# sensorFreezer.net
KiCad netlist of a schematic drawn in EAGLE
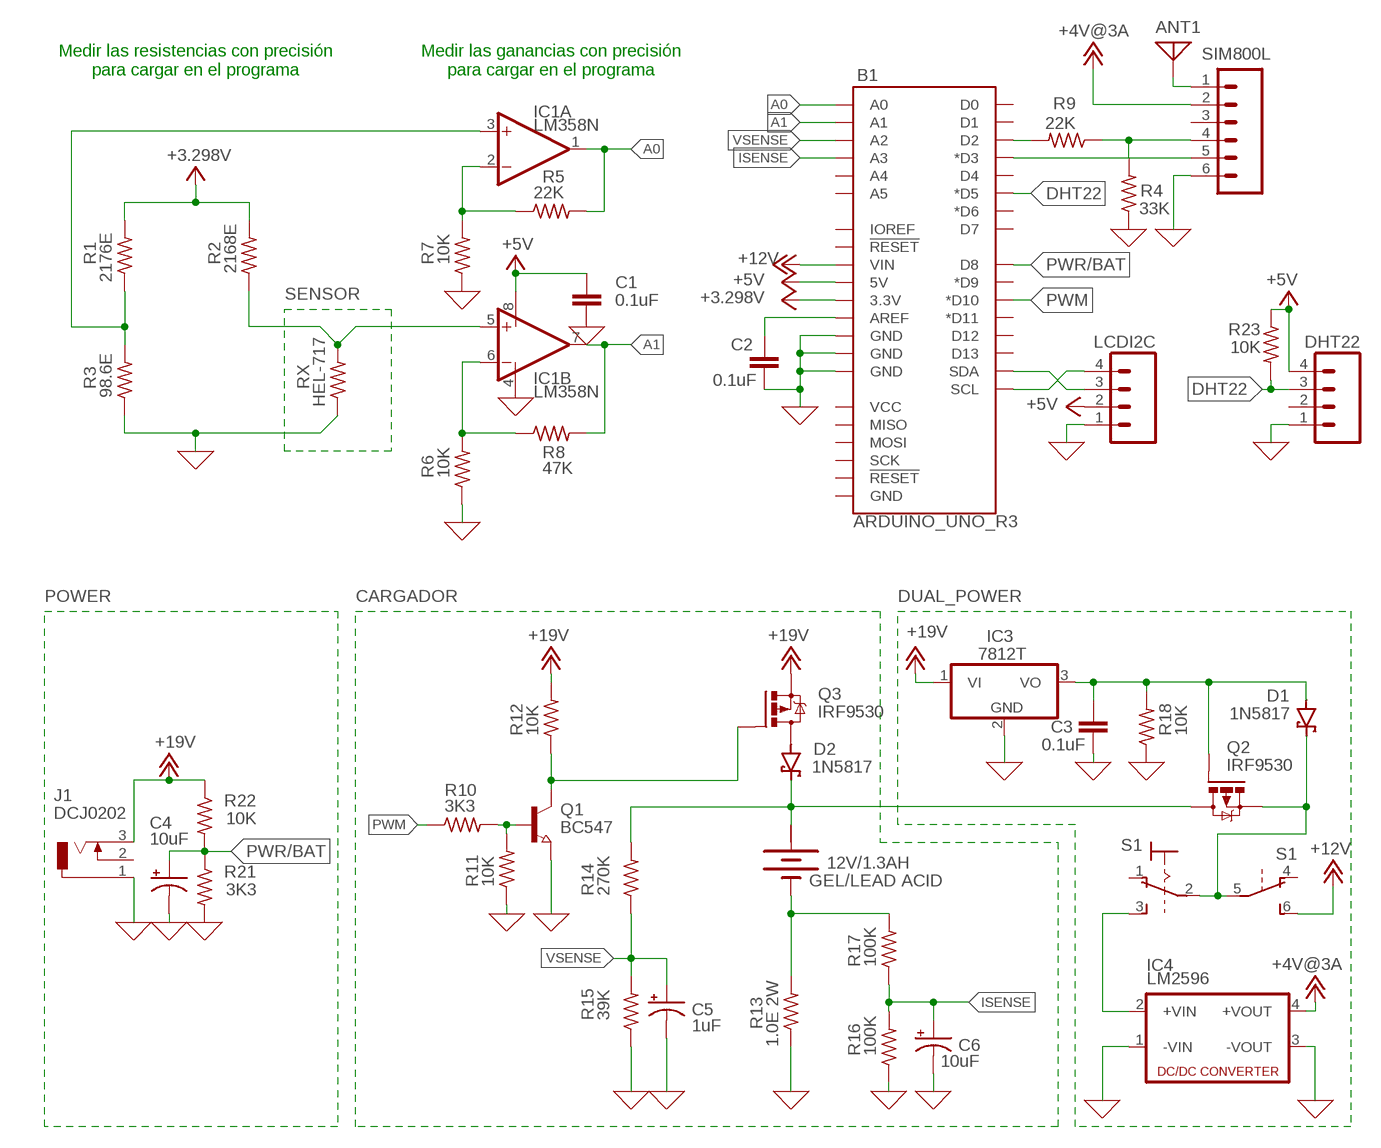
[diagram p0: schematic, sheet 1]

(export (version "E")
  (design (tool "Eeschema 10.0.6"))
  (components
    (comp (ref "12V/1.3AH")
      (value "GEL/LEAD ACID")
      (footprint "eagle-import:BATTERY")
      (libsource (lib "eagle-import") (part "BATTERY"))
    )
    (comp (ref "ANT1")
      (value "ANTENNA")
      (footprint "eagle-import:PAD-01")
      (libsource (lib "eagle-import") (part "ANTENNA"))
    )
    (comp (ref "B1")
      (value "ARDUINO_UNO_R3")
      (footprint "eagle-import:ARDUINO_R3")
      (libsource (lib "eagle-import") (part "ARDUINO_UNO_R3"))
    )
    (comp (ref "C1")
      (value "0.1uF")
      (footprint "eagle-import:C2.5-3")
      (libsource (lib "eagle-import") (part "C2,5-3"))
    )
    (comp (ref "C2")
      (value "0.1uF")
      (footprint "eagle-import:C2.5-3")
      (libsource (lib "eagle-import") (part "C2,5-3"))
    )
    (comp (ref "C3")
      (value "0.1uF")
      (footprint "eagle-import:C2.5-3")
      (libsource (lib "eagle-import") (part "C2,5-3"))
    )
    (comp (ref "C4")
      (value "10uF")
      (footprint "eagle-import:085CS_1AR")
      (libsource (lib "eagle-import") (part "CPOL-US085CS-1AR"))
    )
    (comp (ref "C5")
      (value "1uF")
      (footprint "eagle-import:085CS_1AR")
      (libsource (lib "eagle-import") (part "CPOL-US085CS-1AR"))
    )
    (comp (ref "C6")
      (value "10uF")
      (footprint "eagle-import:085CS_1AR")
      (libsource (lib "eagle-import") (part "CPOL-US085CS-1AR"))
    )
    (comp (ref "D1")
      (value "1N5817")
      (footprint "eagle-import:DO41-7.6")
      (libsource (lib "eagle-import") (part "1N5819-B"))
    )
    (comp (ref "D2")
      (value "1N5817")
      (footprint "eagle-import:DO41-7.6")
      (libsource (lib "eagle-import") (part "1N5819-B"))
    )
    (comp (ref "DHT22")
      (value "M04")
      (footprint "eagle-import:04P")
      (libsource (lib "eagle-import") (part "M04"))
    )
    (comp (ref "IC1")
      (value "LM358N")
      (footprint "eagle-import:DIL08")
      (libsource (lib "eagle-import") (part "LM358N"))
    )
    (comp (ref "IC3")
      (value "7812T")
      (footprint "eagle-import:TO220H")
      (libsource (lib "eagle-import") (part "78T12"))
    )
    (comp (ref "IC4")
      (value "LM2596")
      (footprint "eagle-import:NME")
      (fields (field (name "MF") "C & D TECHNOLOGIES, INC") (field (name "MPN") "NME1205D"))
      (libsource (lib "eagle-import") (part "NME"))
    )
    (comp (ref "J1")
      (value "DCJ0202")
      (footprint "eagle-import:DCJ0202")
      (libsource (lib "eagle-import") (part "DCJ0202"))
    )
    (comp (ref "LCDI2C")
      (value "M04")
      (footprint "eagle-import:04P")
      (libsource (lib "eagle-import") (part "M04"))
    )
    (comp (ref "Q1")
      (value "BC547")
      (footprint "eagle-import:SOT23")
      (libsource (lib "eagle-import") (part "NPN-TRANSISTOR_SOT23"))
    )
    (comp (ref "Q2")
      (value "IRF9530")
      (footprint "eagle-import:TO220BV")
      (libsource (lib "eagle-import") (part "IRF9530"))
    )
    (comp (ref "Q3")
      (value "IRF9530")
      (footprint "eagle-import:TO220BV")
      (libsource (lib "eagle-import") (part "IRF9530"))
    )
    (comp (ref "R1")
      (value "2176E")
      (footprint "eagle-import:0204_5")
      (libsource (lib "eagle-import") (part "R-US_0204/5"))
    )
    (comp (ref "R2")
      (value "2168E")
      (footprint "eagle-import:0204_5")
      (libsource (lib "eagle-import") (part "R-US_0204/5"))
    )
    (comp (ref "R3")
      (value "98.6E")
      (footprint "eagle-import:0204_5")
      (libsource (lib "eagle-import") (part "R-US_0204/5"))
    )
    (comp (ref "R4")
      (value "33K")
      (footprint "eagle-import:0204_5")
      (libsource (lib "eagle-import") (part "R-US_0204/5"))
    )
    (comp (ref "R5")
      (value "22K")
      (footprint "eagle-import:0204_5")
      (libsource (lib "eagle-import") (part "R-US_0204/5"))
    )
    (comp (ref "R6")
      (value "10K")
      (footprint "eagle-import:0204_5")
      (libsource (lib "eagle-import") (part "R-US_0204/5"))
    )
    (comp (ref "R7")
      (value "10K")
      (footprint "eagle-import:0204_5")
      (libsource (lib "eagle-import") (part "R-US_0204/5"))
    )
    (comp (ref "R8")
      (value "47K")
      (footprint "eagle-import:0204_5")
      (libsource (lib "eagle-import") (part "R-US_0204/5"))
    )
    (comp (ref "R9")
      (value "22K")
      (footprint "eagle-import:0204_5")
      (libsource (lib "eagle-import") (part "R-US_0204/5"))
    )
    (comp (ref "R10")
      (value "3K3")
      (footprint "eagle-import:0204_5")
      (libsource (lib "eagle-import") (part "R-US_0204/5"))
    )
    (comp (ref "R11")
      (value "10K")
      (footprint "eagle-import:0204_5")
      (libsource (lib "eagle-import") (part "R-US_0204/5"))
    )
    (comp (ref "R12")
      (value "10K")
      (footprint "eagle-import:0204_5")
      (libsource (lib "eagle-import") (part "R-US_0204/5"))
    )
    (comp (ref "R13")
      (value "1.0E 2W")
      (footprint "eagle-import:0204_5")
      (libsource (lib "eagle-import") (part "R-US_0204/5"))
    )
    (comp (ref "R14")
      (value "270K")
      (footprint "eagle-import:0204_5")
      (libsource (lib "eagle-import") (part "R-US_0204/5"))
    )
    (comp (ref "R15")
      (value "39K")
      (footprint "eagle-import:0204_5")
      (libsource (lib "eagle-import") (part "R-US_0204/5"))
    )
    (comp (ref "R16")
      (value "100K")
      (footprint "eagle-import:0204_5")
      (libsource (lib "eagle-import") (part "R-US_0204/5"))
    )
    (comp (ref "R17")
      (value "100K")
      (footprint "eagle-import:0204_5")
      (libsource (lib "eagle-import") (part "R-US_0204/5"))
    )
    (comp (ref "R18")
      (value "10K")
      (footprint "eagle-import:0204_5")
      (libsource (lib "eagle-import") (part "R-US_0204/5"))
    )
    (comp (ref "R21")
      (value "3K3")
      (footprint "eagle-import:0204_5")
      (libsource (lib "eagle-import") (part "R-US_0204/5"))
    )
    (comp (ref "R22")
      (value "10K")
      (footprint "eagle-import:0204_5")
      (libsource (lib "eagle-import") (part "R-US_0204/5"))
    )
    (comp (ref "R23")
      (value "10K")
      (footprint "eagle-import:0204_5")
      (libsource (lib "eagle-import") (part "R-US_0204/5"))
    )
    (comp (ref "RX")
      (value "HEL-717")
      (footprint "eagle-import:0204_5")
      (libsource (lib "eagle-import") (part "R-US_0204/5"))
    )
    (comp (ref "S1")
      (value "320-938")
      (footprint "eagle-import:320-938")
      (libsource (lib "eagle-import") (part "320-938"))
    )
    (comp (ref "SIM800L")
      (value "M06")
      (footprint "eagle-import:06P")
      (libsource (lib "eagle-import") (part "M06"))
    )
  )
  (nets
    (net (code "1") (name "+3.298V") (class "Default")
      (node (ref "B1") (pin "3.3V") (pinfunction "3.3V_3.3V") (pintype "bidirectional"))
      (node (ref "R1") (pin "2") (pinfunction "2_2") (pintype "passive"))
      (node (ref "R2") (pin "2") (pinfunction "2_2") (pintype "passive"))
    )
    (net (code "2") (name "+5V") (class "Default")
      (node (ref "B1") (pin "5V") (pinfunction "5V_5V") (pintype "bidirectional"))
      (node (ref "C1") (pin "1") (pinfunction "1_1") (pintype "passive"))
      (node (ref "DHT22") (pin "4") (pinfunction "4_4") (pintype "passive"))
      (node (ref "IC1") (pin "8") (pinfunction "V+_8") (pintype "power_in"))
      (node (ref "LCDI2C") (pin "2") (pinfunction "2_2") (pintype "passive"))
      (node (ref "R23") (pin "1") (pinfunction "1_1") (pintype "passive"))
    )
    (net (code "3") (name "+12V") (class "Default")
      (node (ref "B1") (pin "VIN") (pinfunction "VIN_VIN") (pintype "bidirectional"))
      (node (ref "IC3") (pin "1") (pinfunction "VI_1") (pintype "input"))
      (node (ref "IC4") (pin "4") (pinfunction "+VOUT_4") (pintype "passive"))
      (node (ref "J1") (pin "3") (pinfunction "3_3") (pintype "passive"))
      (node (ref "Q3") (pin "S") (pinfunction "S_S") (pintype "passive"))
      (node (ref "R12") (pin "2") (pinfunction "2_2") (pintype "passive"))
      (node (ref "R22") (pin "1") (pinfunction "1_1") (pintype "passive"))
      (node (ref "S1") (pin "6") (pinfunction "S_6") (pintype "passive"))
      (node (ref "SIM800L") (pin "2") (pinfunction "2_2") (pintype "passive"))
    )
    (net (code "4") (name "/+") (class "Default")
      (node (ref "12V/1.3AH") (pin "+@1") (pinfunction "+_+@1") (pintype "power_in"))
    )
    (net (code "9") (name "A0") (class "Default")
      (node (ref "B1") (pin "A0") (pinfunction "A0_A0") (pintype "bidirectional"))
      (node (ref "IC1") (pin "1") (pinfunction "OUT_1") (pintype "output"))
      (node (ref "R5") (pin "2") (pinfunction "2_2") (pintype "passive"))
    )
    (net (code "10") (name "A1") (class "Default")
      (node (ref "B1") (pin "A1") (pinfunction "A1_A1") (pintype "bidirectional"))
      (node (ref "IC1") (pin "7") (pinfunction "OUT_7") (pintype "output"))
      (node (ref "R8") (pin "2") (pinfunction "2_2") (pintype "passive"))
    )
    (net (code "11") (name "DHT22") (class "Default")
      (node (ref "B1") (pin "D5") (pinfunction "*D5_D5") (pintype "bidirectional"))
      (node (ref "DHT22") (pin "3") (pinfunction "3_3") (pintype "passive"))
      (node (ref "R23") (pin "2") (pinfunction "2_2") (pintype "passive"))
    )
    (net (code "12") (name "GND") (class "Default")
      (node (ref "B1") (pin "GND@2") (pinfunction "GND_GND@2") (pintype "bidirectional"))
      (node (ref "B1") (pin "GND@3") (pinfunction "GND_GND@3") (pintype "bidirectional"))
      (node (ref "B1") (pin "GND@4") (pinfunction "GND_GND@4") (pintype "bidirectional"))
      (node (ref "C1") (pin "2") (pinfunction "2_2") (pintype "passive"))
      (node (ref "C2") (pin "2") (pinfunction "2_2") (pintype "passive"))
      (node (ref "C3") (pin "2") (pinfunction "2_2") (pintype "passive"))
      (node (ref "C4") (pin "-") (pinfunction "-_-") (pintype "passive"))
      (node (ref "C5") (pin "-") (pinfunction "-_-") (pintype "passive"))
      (node (ref "C6") (pin "-") (pinfunction "-_-") (pintype "passive"))
      (node (ref "DHT22") (pin "1") (pinfunction "1_1") (pintype "passive"))
      (node (ref "IC1") (pin "4") (pinfunction "V-_4") (pintype "power_in"))
      (node (ref "IC3") (pin "2") (pinfunction "GND_2") (pintype "passive"))
      (node (ref "IC4") (pin "1") (pinfunction "-VIN_1") (pintype "passive"))
      (node (ref "IC4") (pin "3") (pinfunction "-VOUT_3") (pintype "passive"))
      (node (ref "J1") (pin "1") (pinfunction "1_1") (pintype "passive"))
      (node (ref "LCDI2C") (pin "1") (pinfunction "1_1") (pintype "passive"))
      (node (ref "Q1") (pin "2") (pinfunction "E_2") (pintype "passive"))
      (node (ref "R11") (pin "1") (pinfunction "1_1") (pintype "passive"))
      (node (ref "R13") (pin "1") (pinfunction "1_1") (pintype "passive"))
      (node (ref "R15") (pin "1") (pinfunction "1_1") (pintype "passive"))
      (node (ref "R16") (pin "1") (pinfunction "1_1") (pintype "passive"))
      (node (ref "R18") (pin "1") (pinfunction "1_1") (pintype "passive"))
      (node (ref "R21") (pin "2") (pinfunction "2_2") (pintype "passive"))
      (node (ref "R3") (pin "1") (pinfunction "1_1") (pintype "passive"))
      (node (ref "R4") (pin "1") (pinfunction "1_1") (pintype "passive"))
      (node (ref "R6") (pin "1") (pinfunction "1_1") (pintype "passive"))
      (node (ref "R7") (pin "1") (pinfunction "1_1") (pintype "passive"))
      (node (ref "RX") (pin "1") (pinfunction "1_1") (pintype "passive"))
      (node (ref "SIM800L") (pin "6") (pinfunction "6_6") (pintype "passive"))
    )
    (net (code "13") (name "ISENSE") (class "Default")
      (node (ref "B1") (pin "A3") (pinfunction "A3_A3") (pintype "bidirectional"))
      (node (ref "C6") (pin "+") (pinfunction "+_+") (pintype "passive"))
      (node (ref "R16") (pin "2") (pinfunction "2_2") (pintype "passive"))
      (node (ref "R17") (pin "1") (pinfunction "1_1") (pintype "passive"))
    )
    (net (code "14") (name "Net-(12V/1.3AH-Pad+)") (class "Default")
      (node (ref "12V/1.3AH") (pin "+") (pinfunction "+_+") (pintype "power_in"))
      (node (ref "D2") (pin "C") (pinfunction "C_C") (pintype "passive"))
      (node (ref "Q2") (pin "D") (pinfunction "D_D") (pintype "passive"))
      (node (ref "R14") (pin "2") (pinfunction "2_2") (pintype "passive"))
    )
    (net (code "15") (name "Net-(12V/1.3AH-Pad-)") (class "Default")
      (node (ref "12V/1.3AH") (pin "-") (pinfunction "-_-") (pintype "power_in"))
      (node (ref "R13") (pin "2") (pinfunction "2_2") (pintype "passive"))
      (node (ref "R17") (pin "2") (pinfunction "2_2") (pintype "passive"))
    )
    (net (code "16") (name "Net-(ANT1-Pad1)") (class "Default")
      (node (ref "ANT1") (pin "1") (pinfunction "1_1") (pintype "output"))
      (node (ref "SIM800L") (pin "1") (pinfunction "1_1") (pintype "passive"))
    )
    (net (code "17") (name "Net-(B1-*D3)") (class "Default")
      (node (ref "B1") (pin "D3") (pinfunction "*D3_D3") (pintype "bidirectional"))
      (node (ref "SIM800L") (pin "5") (pinfunction "5_5") (pintype "passive"))
    )
    (net (code "18") (name "Net-(B1-PadAREF)") (class "Default")
      (node (ref "B1") (pin "AREF") (pinfunction "AREF_AREF") (pintype "bidirectional"))
      (node (ref "C2") (pin "1") (pinfunction "1_1") (pintype "passive"))
    )
    (net (code "19") (name "Net-(B1-PadD2)") (class "Default")
      (node (ref "B1") (pin "D2") (pinfunction "D2_D2") (pintype "bidirectional"))
      (node (ref "R9") (pin "2") (pinfunction "2_2") (pintype "passive"))
    )
    (net (code "20") (name "Net-(B1-PadSCL)") (class "Default")
      (node (ref "B1") (pin "SCL") (pinfunction "SCL_SCL") (pintype "bidirectional"))
      (node (ref "LCDI2C") (pin "4") (pinfunction "4_4") (pintype "passive"))
    )
    (net (code "21") (name "Net-(B1-PadSDA)") (class "Default")
      (node (ref "B1") (pin "SDA") (pinfunction "SDA_SDA") (pintype "bidirectional"))
      (node (ref "LCDI2C") (pin "3") (pinfunction "3_3") (pintype "passive"))
    )
    (net (code "22") (name "Net-(D2-PadA)") (class "Default")
      (node (ref "D2") (pin "A") (pinfunction "A_A") (pintype "passive"))
      (node (ref "Q3") (pin "D") (pinfunction "D_D") (pintype "passive"))
    )
    (net (code "23") (name "Net-(IC1A-+IN)") (class "Default")
      (node (ref "IC1") (pin "3") (pinfunction "+IN_3") (pintype "input"))
      (node (ref "R1") (pin "1") (pinfunction "1_1") (pintype "passive"))
      (node (ref "R3") (pin "2") (pinfunction "2_2") (pintype "passive"))
    )
    (net (code "24") (name "Net-(IC1A--IN)") (class "Default")
      (node (ref "IC1") (pin "2") (pinfunction "-IN_2") (pintype "input"))
      (node (ref "R5") (pin "1") (pinfunction "1_1") (pintype "passive"))
      (node (ref "R7") (pin "2") (pinfunction "2_2") (pintype "passive"))
    )
    (net (code "25") (name "Net-(IC1B-+IN)") (class "Default")
      (node (ref "IC1") (pin "5") (pinfunction "+IN_5") (pintype "input"))
      (node (ref "R2") (pin "1") (pinfunction "1_1") (pintype "passive"))
      (node (ref "RX") (pin "2") (pinfunction "2_2") (pintype "passive"))
    )
    (net (code "26") (name "Net-(IC1B--IN)") (class "Default")
      (node (ref "IC1") (pin "6") (pinfunction "-IN_6") (pintype "input"))
      (node (ref "R6") (pin "2") (pinfunction "2_2") (pintype "passive"))
      (node (ref "R8") (pin "1") (pinfunction "1_1") (pintype "passive"))
    )
    (net (code "27") (name "Net-(IC3-VO)") (class "Default")
      (node (ref "C3") (pin "1") (pinfunction "1_1") (pintype "passive"))
      (node (ref "D1") (pin "A") (pinfunction "A_A") (pintype "passive"))
      (node (ref "IC3") (pin "3") (pinfunction "VO_3") (pintype "passive"))
      (node (ref "Q2") (pin "G") (pinfunction "G_G") (pintype "passive"))
      (node (ref "R18") (pin "2") (pinfunction "2_2") (pintype "passive"))
    )
    (net (code "28") (name "Net-(IC4-+VIN)") (class "Default")
      (node (ref "IC4") (pin "2") (pinfunction "+VIN_2") (pintype "passive"))
      (node (ref "S1") (pin "3") (pinfunction "S_3") (pintype "passive"))
    )
    (net (code "29") (name "Net-(Q1-B)") (class "Default")
      (node (ref "Q1") (pin "1") (pinfunction "B_1") (pintype "passive"))
      (node (ref "R10") (pin "2") (pinfunction "2_2") (pintype "passive"))
      (node (ref "R11") (pin "2") (pinfunction "2_2") (pintype "passive"))
    )
    (net (code "30") (name "Net-(Q1-C)") (class "Default")
      (node (ref "Q1") (pin "3") (pinfunction "C_3") (pintype "passive"))
      (node (ref "Q3") (pin "G") (pinfunction "G_G") (pintype "passive"))
      (node (ref "R12") (pin "1") (pinfunction "1_1") (pintype "passive"))
    )
    (net (code "31") (name "Net-(R4-Pad2)") (class "Default")
      (node (ref "R4") (pin "2") (pinfunction "2_2") (pintype "passive"))
      (node (ref "R9") (pin "1") (pinfunction "1_1") (pintype "passive"))
      (node (ref "SIM800L") (pin "4") (pinfunction "4_4") (pintype "passive"))
    )
    (net (code "32") (name "Net-(S1A-P)") (class "Default")
      (node (ref "D1") (pin "C") (pinfunction "C_C") (pintype "passive"))
      (node (ref "Q2") (pin "S") (pinfunction "S_S") (pintype "passive"))
      (node (ref "S1") (pin "2") (pinfunction "P_2") (pintype "passive"))
      (node (ref "S1") (pin "5") (pinfunction "P_5") (pintype "passive"))
    )
    (net (code "33") (name "PWM") (class "Default")
      (node (ref "B1") (pin "D10") (pinfunction "*D10_D10") (pintype "bidirectional"))
      (node (ref "R10") (pin "1") (pinfunction "1_1") (pintype "passive"))
    )
    (net (code "34") (name "PWR{slash}BAT") (class "Default")
      (node (ref "B1") (pin "D8") (pinfunction "D8_D8") (pintype "bidirectional"))
      (node (ref "C4") (pin "+") (pinfunction "+_+") (pintype "passive"))
      (node (ref "R21") (pin "1") (pinfunction "1_1") (pintype "passive"))
      (node (ref "R22") (pin "2") (pinfunction "2_2") (pintype "passive"))
    )
    (net (code "35") (name "VSENSE") (class "Default")
      (node (ref "B1") (pin "A2") (pinfunction "A2_A2") (pintype "bidirectional"))
      (node (ref "C5") (pin "+") (pinfunction "+_+") (pintype "passive"))
      (node (ref "R14") (pin "1") (pinfunction "1_1") (pintype "passive"))
      (node (ref "R15") (pin "2") (pinfunction "2_2") (pintype "passive"))
    )
    (net (code "36") (name "unconnected-(B1-*D6-PadD6)") (class "Default")
      (node (ref "B1") (pin "D6") (pinfunction "*D6_D6") (pintype "bidirectional"))
    )
    (net (code "37") (name "unconnected-(B1-*D9-PadD9)") (class "Default")
      (node (ref "B1") (pin "D9") (pinfunction "*D9_D9") (pintype "bidirectional"))
    )
    (net (code "38") (name "unconnected-(B1-*D11-PadD11)") (class "Default")
      (node (ref "B1") (pin "D11") (pinfunction "*D11_D11") (pintype "bidirectional"))
    )
    (net (code "39") (name "unconnected-(B1-GND-PadGND@1)") (class "Default")
      (node (ref "B1") (pin "GND@1") (pinfunction "GND_GND@1") (pintype "bidirectional"))
    )
    (net (code "40") (name "unconnected-(B1-PadA4)") (class "Default")
      (node (ref "B1") (pin "A4") (pinfunction "A4_A4") (pintype "bidirectional"))
    )
    (net (code "41") (name "unconnected-(B1-PadA5)") (class "Default")
      (node (ref "B1") (pin "A5") (pinfunction "A5_A5") (pintype "bidirectional"))
    )
    (net (code "42") (name "unconnected-(B1-PadD0)") (class "Default")
      (node (ref "B1") (pin "D0") (pinfunction "D0_D0") (pintype "bidirectional"))
    )
    (net (code "43") (name "unconnected-(B1-PadD1)") (class "Default")
      (node (ref "B1") (pin "D1") (pinfunction "D1_D1") (pintype "bidirectional"))
    )
    (net (code "44") (name "unconnected-(B1-PadD4)") (class "Default")
      (node (ref "B1") (pin "D4") (pinfunction "D4_D4") (pintype "bidirectional"))
    )
    (net (code "45") (name "unconnected-(B1-PadD7)") (class "Default")
      (node (ref "B1") (pin "D7") (pinfunction "D7_D7") (pintype "bidirectional"))
    )
    (net (code "46") (name "unconnected-(B1-PadD12)") (class "Default")
      (node (ref "B1") (pin "D12") (pinfunction "D12_D12") (pintype "bidirectional"))
    )
    (net (code "47") (name "unconnected-(B1-PadD13)") (class "Default")
      (node (ref "B1") (pin "D13") (pinfunction "D13_D13") (pintype "bidirectional"))
    )
    (net (code "48") (name "unconnected-(B1-PadIOREF)") (class "Default")
      (node (ref "B1") (pin "IOREF") (pinfunction "IOREF_IOREF") (pintype "bidirectional"))
    )
    (net (code "49") (name "unconnected-(B1-PadMISO)") (class "Default")
      (node (ref "B1") (pin "MISO") (pinfunction "MISO_MISO") (pintype "bidirectional"))
    )
    (net (code "50") (name "unconnected-(B1-PadMOSI)") (class "Default")
      (node (ref "B1") (pin "MOSI") (pinfunction "MOSI_MOSI") (pintype "bidirectional"))
    )
    (net (code "51") (name "unconnected-(B1-PadSCK)") (class "Default")
      (node (ref "B1") (pin "SCK") (pinfunction "SCK_SCK") (pintype "bidirectional"))
    )
    (net (code "52") (name "unconnected-(B1-PadVCC)") (class "Default")
      (node (ref "B1") (pin "VCC") (pinfunction "VCC_VCC") (pintype "bidirectional"))
    )
    (net (code "53") (name "unconnected-(B1-~{RESET}-PadRESET@1)") (class "Default")
      (node (ref "B1") (pin "RESET@1") (pinfunction "~{RESET}_RESET@1") (pintype "bidirectional"))
    )
    (net (code "54") (name "unconnected-(B1-~{RESET}-PadRESET@2)") (class "Default")
      (node (ref "B1") (pin "RESET@2") (pinfunction "~{RESET}_RESET@2") (pintype "bidirectional"))
    )
    (net (code "55") (name "unconnected-(DHT22-Pad2)") (class "Default")
      (node (ref "DHT22") (pin "2") (pinfunction "2_2") (pintype "passive"))
    )
    (net (code "56") (name "unconnected-(J1-Pad2)") (class "Default")
      (node (ref "J1") (pin "2") (pinfunction "2_2") (pintype "passive"))
    )
    (net (code "57") (name "unconnected-(S1A-O-Pad1)") (class "Default")
      (node (ref "S1") (pin "1") (pinfunction "O_1") (pintype "passive"))
    )
    (net (code "58") (name "unconnected-(S1B-O-Pad4)") (class "Default")
      (node (ref "S1") (pin "4") (pinfunction "O_4") (pintype "passive"))
    )
    (net (code "59") (name "unconnected-(SIM800L-Pad3)") (class "Default")
      (node (ref "SIM800L") (pin "3") (pinfunction "3_3") (pintype "passive"))
    )
  )
)
